# Memory_Nor_Flash.net
KiCad netlist of a schematic drawn in Altium Designer
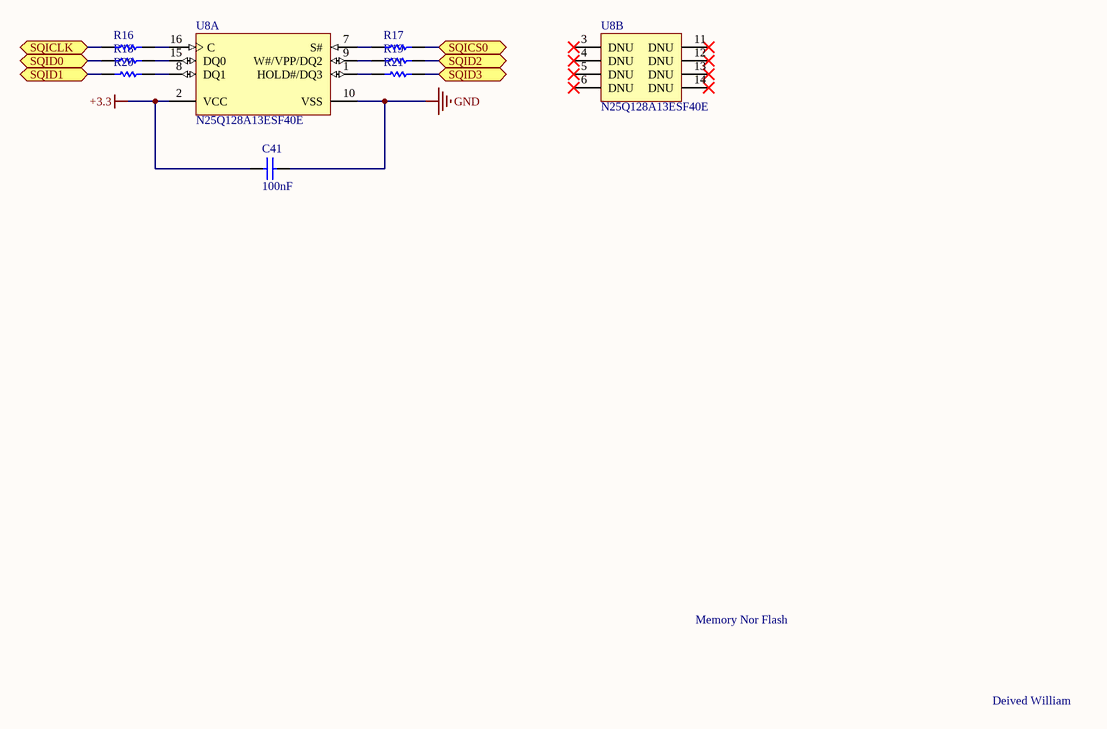
[diagram p0: Memory Nor Flash.SchDoc]

(export (version "E")
  (design (tool "Eeschema 10.0.6"))
  (components
    (comp (ref "C41")
      (value "100nF")
      (footprint "WCAP-CSGP_0603, 1.6x0.8x0.8mm_Reflow")
      (description "WCAP-CSGP Ceramic Capacitors, size 0603, 1.6x0.8x0.8mm, 10V, X7R, 100nF")
      (fields (field (name "PART NUMBER") "885012206020") (field (name "PUBLISHER") "Wurth Elektronik"))
      (libsource (lib "Altium_WCAP-CSGP (rev17a)") (part "885012206020"))
    )
    (comp (ref "R16")
      (value "50R")
      (footprint "3-0603")
      (fields (field (name "PUBLISHER") "Altium Limited"))
      (libsource (lib "Panasonic Resistor") (part "ERJ3RE"))
    )
    (comp (ref "R17")
      (value "50R")
      (footprint "3-0603")
      (fields (field (name "PUBLISHER") "Altium Limited"))
      (libsource (lib "Panasonic Resistor") (part "ERJ3RE"))
    )
    (comp (ref "R18")
      (value "50R")
      (footprint "3-0603")
      (fields (field (name "PUBLISHER") "Altium Limited"))
      (libsource (lib "Panasonic Resistor") (part "ERJ3RE"))
    )
    (comp (ref "R19")
      (value "50R")
      (footprint "3-0603")
      (fields (field (name "PUBLISHER") "Altium Limited"))
      (libsource (lib "Panasonic Resistor") (part "ERJ3RE"))
    )
    (comp (ref "R20")
      (value "50R")
      (footprint "3-0603")
      (fields (field (name "PUBLISHER") "Altium Limited"))
      (libsource (lib "Panasonic Resistor") (part "ERJ3RE"))
    )
    (comp (ref "R21")
      (value "50R")
      (footprint "3-0603")
      (fields (field (name "PUBLISHER") "Altium Limited"))
      (libsource (lib "Panasonic Resistor") (part "ERJ3RE"))
    )
    (comp (ref "U8")
      (value "N25Q128A13ESF40E")
      (footprint "MICT-SF-16_N")
      (fields (field (name "VOLTAGE") "2.7V-3.6V ") (field (name "MANUFACTURER") "Micron"))
      (libsource (lib "Micron Memory Serial NOR Flash") (part "N25Q128A13ESF40E"))
    )
  )
  (nets
    (net (code "1") (name "+3.3") (class "Default")
      (node (ref "C41") (pin "1") (pinfunction "1_1") (pintype "passive"))
      (node (ref "U8") (pin "2") (pinfunction "VCC_2") (pintype "power_in"))
    )
    (net (code "2") (name "/SQICLK") (class "Default")
      (node (ref "R16") (pin "1") (pinfunction "1_1") (pintype "passive"))
    )
    (net (code "3") (name "/SQICS0") (class "Default")
      (node (ref "R17") (pin "2") (pinfunction "2_2") (pintype "passive"))
    )
    (net (code "4") (name "/SQID0") (class "Default")
      (node (ref "R18") (pin "1") (pinfunction "1_1") (pintype "passive"))
    )
    (net (code "5") (name "/SQID1") (class "Default")
      (node (ref "R20") (pin "1") (pinfunction "1_1") (pintype "passive"))
    )
    (net (code "6") (name "/SQID2") (class "Default")
      (node (ref "R19") (pin "2") (pinfunction "2_2") (pintype "passive"))
    )
    (net (code "7") (name "/SQID3") (class "Default")
      (node (ref "R21") (pin "2") (pinfunction "2_2") (pintype "passive"))
    )
    (net (code "8") (name "GND") (class "Default")
      (node (ref "C41") (pin "2") (pinfunction "2_2") (pintype "passive"))
      (node (ref "U8") (pin "10") (pinfunction "VSS_10") (pintype "power_in"))
    )
    (net (code "9") (name "Net-(U8A-C)") (class "Default")
      (node (ref "R16") (pin "2") (pinfunction "2_2") (pintype "passive"))
      (node (ref "U8") (pin "16") (pinfunction "C_16") (pintype "input"))
    )
    (net (code "10") (name "Net-(U8A-DQ0)") (class "Default")
      (node (ref "R18") (pin "2") (pinfunction "2_2") (pintype "passive"))
      (node (ref "U8") (pin "15") (pinfunction "DQ0_15") (pintype "bidirectional"))
    )
    (net (code "11") (name "Net-(U8A-DQ1)") (class "Default")
      (node (ref "R20") (pin "2") (pinfunction "2_2") (pintype "passive"))
      (node (ref "U8") (pin "8") (pinfunction "DQ1_8") (pintype "bidirectional"))
    )
    (net (code "12") (name "Net-(U8A-HOLD#{slash}DQ3)") (class "Default")
      (node (ref "R21") (pin "1") (pinfunction "1_1") (pintype "passive"))
      (node (ref "U8") (pin "1") (pinfunction "HOLD#/DQ3_1") (pintype "bidirectional"))
    )
    (net (code "13") (name "Net-(U8A-S#)") (class "Default")
      (node (ref "R17") (pin "1") (pinfunction "1_1") (pintype "passive"))
      (node (ref "U8") (pin "7") (pinfunction "S#_7") (pintype "input"))
    )
    (net (code "14") (name "Net-(U8A-W#{slash}VPP{slash}DQ2)") (class "Default")
      (node (ref "R19") (pin "1") (pinfunction "1_1") (pintype "passive"))
      (node (ref "U8") (pin "9") (pinfunction "W#/VPP/DQ2_9") (pintype "bidirectional"))
    )
    (net (code "15") (name "unconnected-(U8B-DNU-Pad3)") (class "Default")
      (node (ref "U8") (pin "3") (pinfunction "DNU_3") (pintype "passive+no_connect"))
    )
    (net (code "16") (name "unconnected-(U8B-DNU-Pad4)") (class "Default")
      (node (ref "U8") (pin "4") (pinfunction "DNU_4") (pintype "passive+no_connect"))
    )
    (net (code "17") (name "unconnected-(U8B-DNU-Pad5)") (class "Default")
      (node (ref "U8") (pin "5") (pinfunction "DNU_5") (pintype "passive+no_connect"))
    )
    (net (code "18") (name "unconnected-(U8B-DNU-Pad6)") (class "Default")
      (node (ref "U8") (pin "6") (pinfunction "DNU_6") (pintype "passive+no_connect"))
    )
    (net (code "19") (name "unconnected-(U8B-DNU-Pad11)") (class "Default")
      (node (ref "U8") (pin "11") (pinfunction "DNU_11") (pintype "passive+no_connect"))
    )
    (net (code "20") (name "unconnected-(U8B-DNU-Pad12)") (class "Default")
      (node (ref "U8") (pin "12") (pinfunction "DNU_12") (pintype "passive+no_connect"))
    )
    (net (code "21") (name "unconnected-(U8B-DNU-Pad13)") (class "Default")
      (node (ref "U8") (pin "13") (pinfunction "DNU_13") (pintype "passive+no_connect"))
    )
    (net (code "22") (name "unconnected-(U8B-DNU-Pad14)") (class "Default")
      (node (ref "U8") (pin "14") (pinfunction "DNU_14") (pintype "passive+no_connect"))
    )
  )
)
